# sch_2023-05-29.net
KiCad netlist of a schematic drawn in Altium Designer
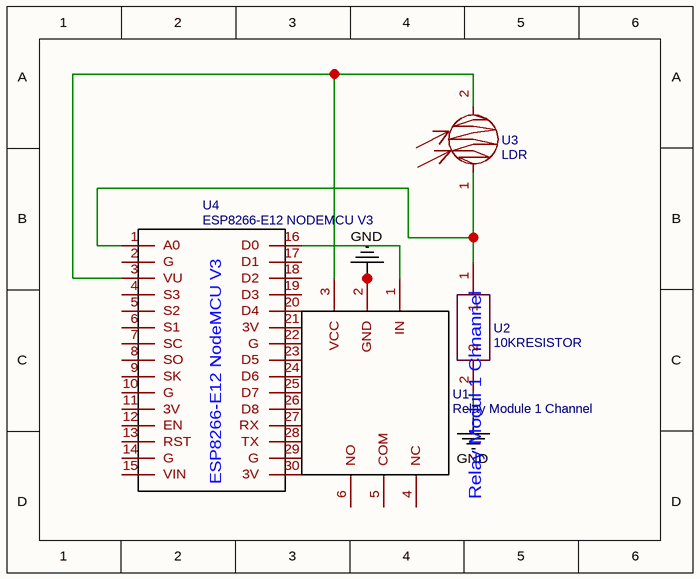
[diagram p0: sch_2023-05-29.schdoc]

(export (version "E")
  (design (tool "Eeschema 10.0.6"))
  (components
    (comp (ref "U1")
      (value "Relay Module 1 Channel")
      (fields
        (field (name "BOM_MANUFACTURER PART") "Relay Module hw-279 2 relays")
        (field (name "CONTRIBUTOR") "Haramu4a")
      )
      (libsource (lib "altium-import") (part "root_3_Relay Module 1 Channel_"))
    )
    (comp (ref "U2")
      (value "10KRESISTOR")
      (fields
        (field (name "BOM_MANUFACTURER PART") "MCMF0W4DF1002A50")
        (field (name "BOM_SUPPLIER PART") "1563077")
        (field (name "CONTRIBUTOR") "alexandriamckie")
      )
      (libsource (lib "altium-import") (part "root_1_10KRESISTOR_"))
    )
    (comp (ref "U3")
      (value "LDR")
      (fields (field (name "CONTRIBUTOR") "PatoViejo"))
      (libsource (lib "altium-import") (part "root_1_LDR_"))
    )
    (comp (ref "U4")
      (value "ESP8266-E12 NODEMCU V3")
      (fields (field (name "CONTRIBUTOR") "sigmur"))
      (libsource (lib "altium-import") (part "root_0_ESP8266-E12 NODEMCU V3_"))
    )
  )
  (nets
    (net (code "1") (name "GND") (class "Default")
      (node (ref "U1") (pin "2") (pinfunction "GND_2") (pintype "passive"))
      (node (ref "U2") (pin "2") (pinfunction "2_2") (pintype "passive"))
    )
    (net (code "2") (name "Net-(U1-IN)") (class "Default")
      (node (ref "U1") (pin "1") (pinfunction "IN_1") (pintype "passive"))
      (node (ref "U4") (pin "16") (pinfunction "D0_16") (pintype "passive"))
    )
    (net (code "3") (name "Net-(U1-VCC)") (class "Default")
      (node (ref "U1") (pin "3") (pinfunction "VCC_3") (pintype "passive"))
      (node (ref "U3") (pin "2") (pinfunction "2_2") (pintype "passive"))
      (node (ref "U4") (pin "3") (pinfunction "VU_3") (pintype "passive"))
    )
    (net (code "4") (name "Net-(U4-A0)") (class "Default")
      (node (ref "U2") (pin "1") (pinfunction "1_1") (pintype "passive"))
      (node (ref "U3") (pin "1") (pinfunction "1_1") (pintype "passive"))
      (node (ref "U4") (pin "1") (pinfunction "A0_1") (pintype "passive"))
    )
    (net (code "5") (name "unconnected-(U1-COM-Pad5)") (class "Default")
      (node (ref "U1") (pin "5") (pinfunction "COM_5") (pintype "passive"))
    )
    (net (code "6") (name "unconnected-(U1-NC-Pad4)") (class "Default")
      (node (ref "U1") (pin "4") (pinfunction "NC_4") (pintype "passive"))
    )
    (net (code "7") (name "unconnected-(U1-NO-Pad6)") (class "Default")
      (node (ref "U1") (pin "6") (pinfunction "NO_6") (pintype "passive"))
    )
    (net (code "8") (name "unconnected-(U4-3V-Pad11)") (class "Default")
      (node (ref "U4") (pin "11") (pinfunction "3V_11") (pintype "passive"))
    )
    (net (code "9") (name "unconnected-(U4-3V-Pad21)") (class "Default")
      (node (ref "U4") (pin "21") (pinfunction "3V_21") (pintype "passive"))
    )
    (net (code "10") (name "unconnected-(U4-3V-Pad30)") (class "Default")
      (node (ref "U4") (pin "30") (pinfunction "3V_30") (pintype "passive"))
    )
    (net (code "11") (name "unconnected-(U4-D1-Pad17)") (class "Default")
      (node (ref "U4") (pin "17") (pinfunction "D1_17") (pintype "passive"))
    )
    (net (code "12") (name "unconnected-(U4-D2-Pad18)") (class "Default")
      (node (ref "U4") (pin "18") (pinfunction "D2_18") (pintype "passive"))
    )
    (net (code "13") (name "unconnected-(U4-D3-Pad19)") (class "Default")
      (node (ref "U4") (pin "19") (pinfunction "D3_19") (pintype "passive"))
    )
    (net (code "14") (name "unconnected-(U4-D4-Pad20)") (class "Default")
      (node (ref "U4") (pin "20") (pinfunction "D4_20") (pintype "passive"))
    )
    (net (code "15") (name "unconnected-(U4-D5-Pad23)") (class "Default")
      (node (ref "U4") (pin "23") (pinfunction "D5_23") (pintype "passive"))
    )
    (net (code "16") (name "unconnected-(U4-D6-Pad24)") (class "Default")
      (node (ref "U4") (pin "24") (pinfunction "D6_24") (pintype "passive"))
    )
    (net (code "17") (name "unconnected-(U4-D7-Pad25)") (class "Default")
      (node (ref "U4") (pin "25") (pinfunction "D7_25") (pintype "passive"))
    )
    (net (code "18") (name "unconnected-(U4-D8-Pad26)") (class "Default")
      (node (ref "U4") (pin "26") (pinfunction "D8_26") (pintype "passive"))
    )
    (net (code "19") (name "unconnected-(U4-EN-Pad12)") (class "Default")
      (node (ref "U4") (pin "12") (pinfunction "EN_12") (pintype "passive"))
    )
    (net (code "20") (name "unconnected-(U4-G-Pad2)") (class "Default")
      (node (ref "U4") (pin "2") (pinfunction "G_2") (pintype "passive"))
    )
    (net (code "21") (name "unconnected-(U4-G-Pad10)") (class "Default")
      (node (ref "U4") (pin "10") (pinfunction "G_10") (pintype "passive"))
    )
    (net (code "22") (name "unconnected-(U4-G-Pad14)") (class "Default")
      (node (ref "U4") (pin "14") (pinfunction "G_14") (pintype "passive"))
    )
    (net (code "23") (name "unconnected-(U4-G-Pad22)") (class "Default")
      (node (ref "U4") (pin "22") (pinfunction "G_22") (pintype "passive"))
    )
    (net (code "24") (name "unconnected-(U4-G-Pad29)") (class "Default")
      (node (ref "U4") (pin "29") (pinfunction "G_29") (pintype "passive"))
    )
    (net (code "25") (name "unconnected-(U4-RST-Pad13)") (class "Default")
      (node (ref "U4") (pin "13") (pinfunction "RST_13") (pintype "passive"))
    )
    (net (code "26") (name "unconnected-(U4-RX-Pad27)") (class "Default")
      (node (ref "U4") (pin "27") (pinfunction "RX_27") (pintype "passive"))
    )
    (net (code "27") (name "unconnected-(U4-S1-Pad6)") (class "Default")
      (node (ref "U4") (pin "6") (pinfunction "S1_6") (pintype "passive"))
    )
    (net (code "28") (name "unconnected-(U4-S2-Pad5)") (class "Default")
      (node (ref "U4") (pin "5") (pinfunction "S2_5") (pintype "passive"))
    )
    (net (code "29") (name "unconnected-(U4-S3-Pad4)") (class "Default")
      (node (ref "U4") (pin "4") (pinfunction "S3_4") (pintype "passive"))
    )
    (net (code "30") (name "unconnected-(U4-SC-Pad7)") (class "Default")
      (node (ref "U4") (pin "7") (pinfunction "SC_7") (pintype "passive"))
    )
    (net (code "31") (name "unconnected-(U4-SK-Pad9)") (class "Default")
      (node (ref "U4") (pin "9") (pinfunction "SK_9") (pintype "passive"))
    )
    (net (code "32") (name "unconnected-(U4-SO-Pad8)") (class "Default")
      (node (ref "U4") (pin "8") (pinfunction "SO_8") (pintype "passive"))
    )
    (net (code "33") (name "unconnected-(U4-TX-Pad28)") (class "Default")
      (node (ref "U4") (pin "28") (pinfunction "TX_28") (pintype "passive"))
    )
    (net (code "34") (name "unconnected-(U4-VIN-Pad15)") (class "Default")
      (node (ref "U4") (pin "15") (pinfunction "VIN_15") (pintype "passive"))
    )
  )
)
